# DAC_GainOutputStage6.net
KiCad netlist of a schematic drawn in EAGLE
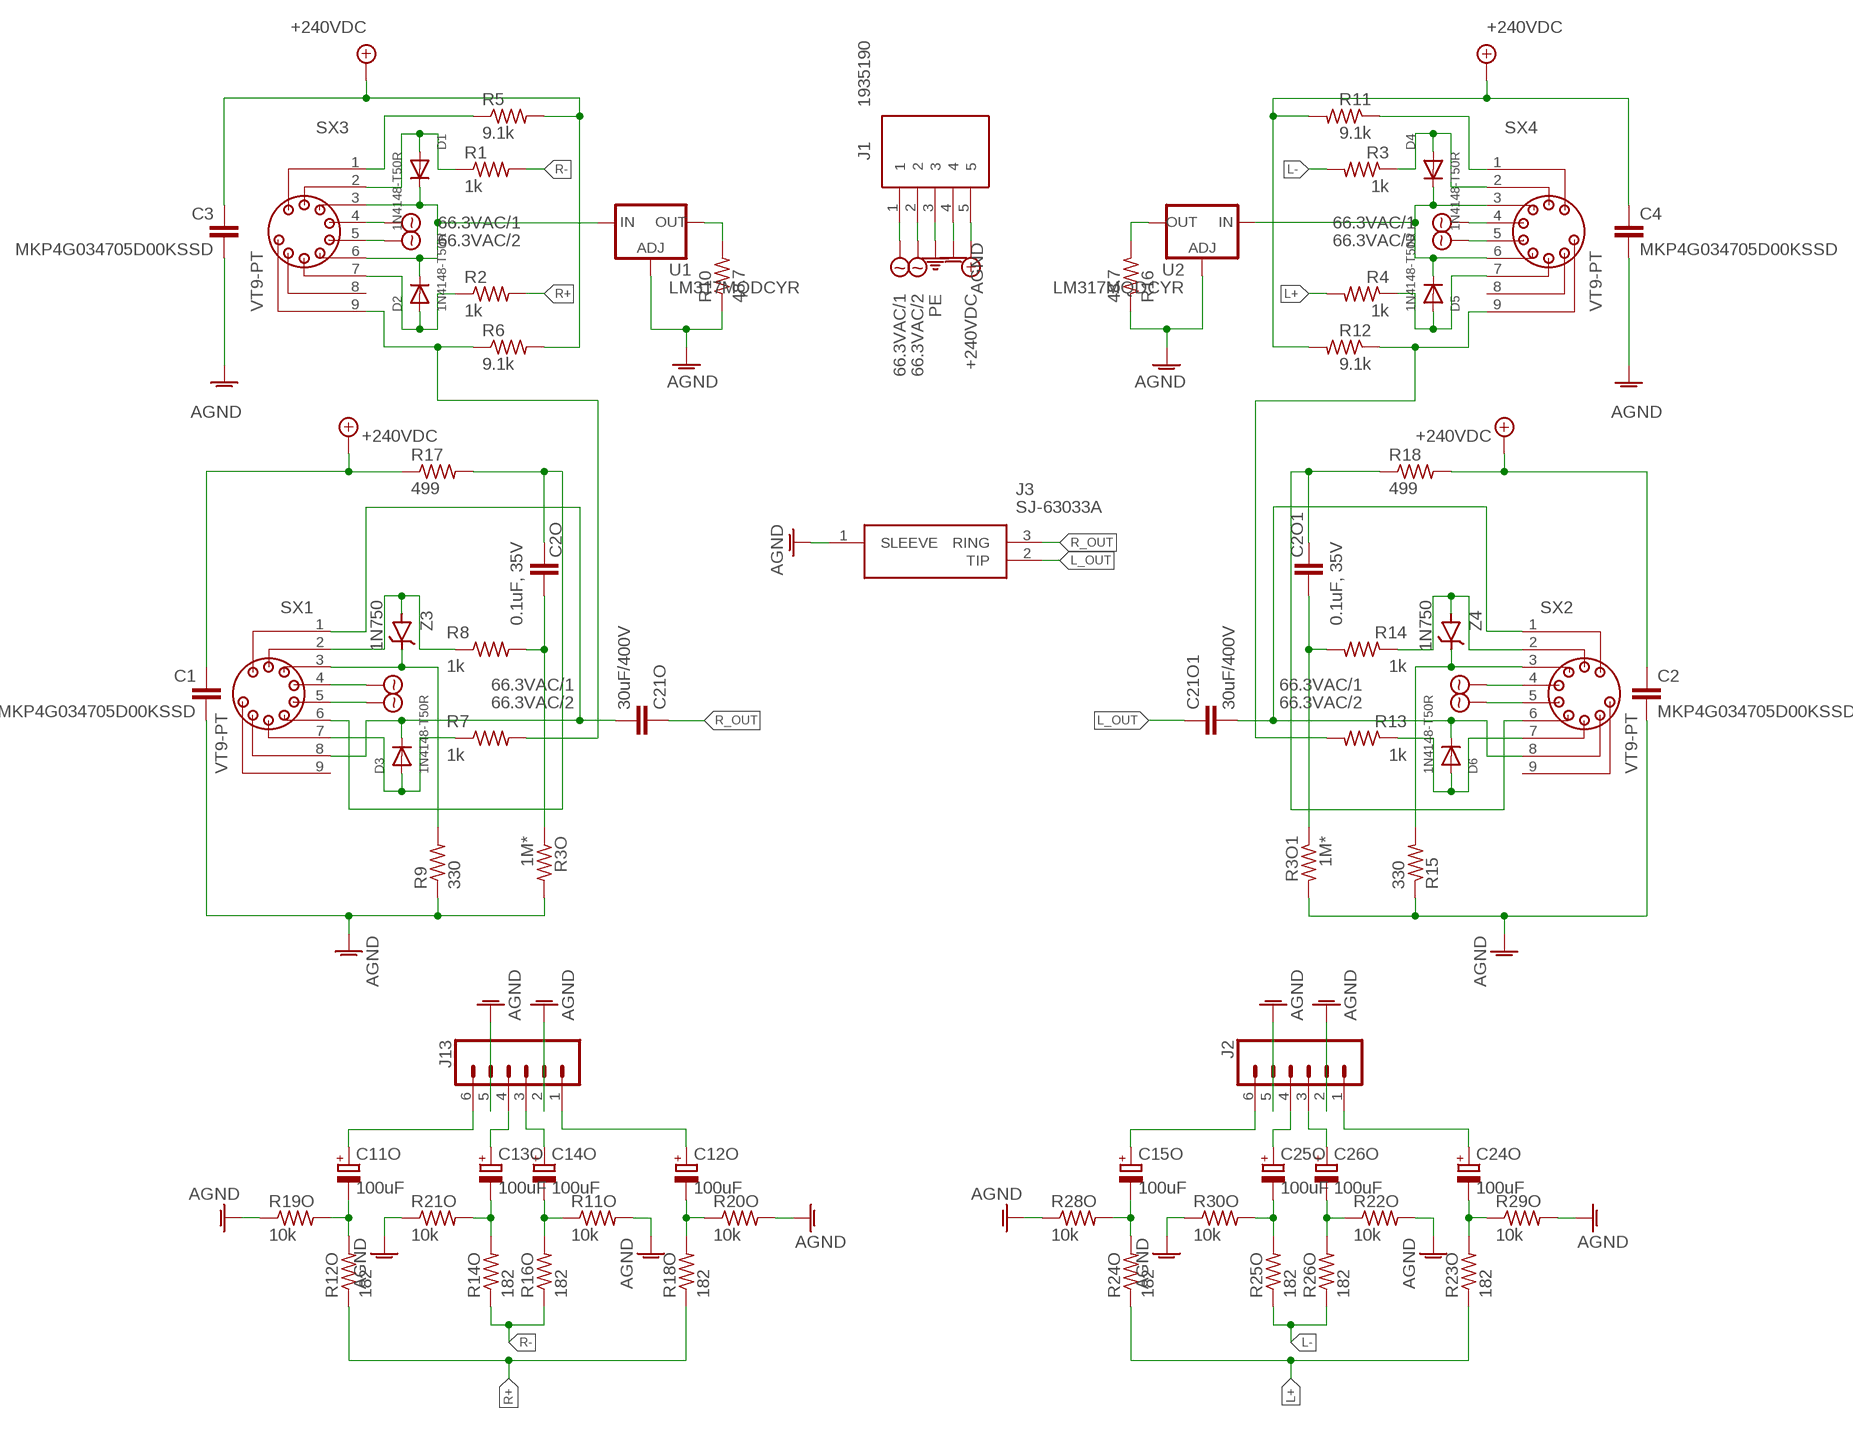
[diagram p0: schematic, sheet 1]

(export (version "E")
  (design (tool "Eeschema 10.0.6"))
  (components
    (comp (ref "C1")
      (value "MKP4G034705D00KSSD")
      (footprint "eagle-import:MKP4G034705D00KSSD")
      (fields (field (name "MOUSER_PART_NUMBER") "505-MKP4G034705DKSSD"))
      (libsource (lib "eagle-import") (part "MKP4G034705D00KSSD"))
    )
    (comp (ref "C2")
      (value "MKP4G034705D00KSSD")
      (footprint "eagle-import:MKP4G034705D00KSSD")
      (fields (field (name "MOUSER_PART_NUMBER") "505-MKP4G034705DKSSD"))
      (libsource (lib "eagle-import") (part "MKP4G034705D00KSSD"))
    )
    (comp (ref "C2O")
      (value "0.1uF, 35V")
      (footprint "eagle-import:MKS4B031002A00JC00")
      (fields
        (field (name "MANUFACTURER_PART_NUMBER") "MKS4B031002A00JC00")
        (field (name "MOUSER_PART_NUMBER") "505-MKS4B0312AJC")
      )
      (libsource (lib "eagle-import") (part "MKS4B031002A00JC00"))
    )
    (comp (ref "C2O1")
      (value "0.1uF, 35V")
      (footprint "eagle-import:MKS4B031002A00JC00")
      (fields
        (field (name "MANUFACTURER_PART_NUMBER") "MKS4B031002A00JC00")
        (field (name "MOUSER_PART_NUMBER") "505-MKS4B0312AJC")
      )
      (libsource (lib "eagle-import") (part "MKS4B031002A00JC00"))
    )
    (comp (ref "C3")
      (value "MKP4G034705D00KSSD")
      (footprint "eagle-import:MKP4G034705D00KSSD")
      (fields (field (name "MOUSER_PART_NUMBER") "505-MKP4G034705DKSSD"))
      (libsource (lib "eagle-import") (part "MKP4G034705D00KSSD"))
    )
    (comp (ref "C4")
      (value "MKP4G034705D00KSSD")
      (footprint "eagle-import:MKP4G034705D00KSSD")
      (fields (field (name "MOUSER_PART_NUMBER") "505-MKP4G034705DKSSD"))
      (libsource (lib "eagle-import") (part "MKP4G034705D00KSSD"))
    )
    (comp (ref "C11O")
      (value "100uF")
      (footprint "eagle-import:CAPPRD350W60D825H1300")
      (fields
        (field (name "ARROW_PART_NUMBER") "UFW1H101MPD1TD")
        (field (name "MOUSER_PART_NUMBER") "647-UFW1H101MPD1TD")
      )
      (libsource (lib "eagle-import") (part "UFW1H101MPD1TD"))
    )
    (comp (ref "C12O")
      (value "100uF")
      (footprint "eagle-import:CAPPRD350W60D825H1300")
      (fields
        (field (name "ARROW_PART_NUMBER") "UFW1H101MPD1TD")
        (field (name "MOUSER_PART_NUMBER") "647-UFW1H101MPD1TD")
      )
      (libsource (lib "eagle-import") (part "UFW1H101MPD1TD"))
    )
    (comp (ref "C13O")
      (value "100uF")
      (footprint "eagle-import:CAPPRD350W60D825H1300")
      (fields
        (field (name "ARROW_PART_NUMBER") "UFW1H101MPD1TD")
        (field (name "MOUSER_PART_NUMBER") "647-UFW1H101MPD1TD")
      )
      (libsource (lib "eagle-import") (part "UFW1H101MPD1TD"))
    )
    (comp (ref "C14O")
      (value "100uF")
      (footprint "eagle-import:CAPPRD350W60D825H1300")
      (fields
        (field (name "ARROW_PART_NUMBER") "UFW1H101MPD1TD")
        (field (name "MOUSER_PART_NUMBER") "647-UFW1H101MPD1TD")
      )
      (libsource (lib "eagle-import") (part "UFW1H101MPD1TD"))
    )
    (comp (ref "C15O")
      (value "100uF")
      (footprint "eagle-import:CAPPRD350W60D825H1300")
      (fields
        (field (name "ARROW_PART_NUMBER") "UFW1H101MPD1TD")
        (field (name "MOUSER_PART_NUMBER") "647-UFW1H101MPD1TD")
      )
      (libsource (lib "eagle-import") (part "UFW1H101MPD1TD"))
    )
    (comp (ref "C21O")
      (value "30uF/400V")
      (footprint "eagle-import:DCP4G053006ID2KSSD")
      (fields
        (field (name "MANUFACTURER_PART_NUMBER") "DCP4G053006ID2KSSD")
        (field (name "MOUSER_PART_NUMBER") "505-DCP4G0536ID2KSSD")
      )
      (libsource (lib "eagle-import") (part "DCP4G053006ID2KSSD"))
    )
    (comp (ref "C21O1")
      (value "30uF/400V")
      (footprint "eagle-import:DCP4G053006ID2KSSD")
      (fields
        (field (name "MANUFACTURER_PART_NUMBER") "DCP4G053006ID2KSSD")
        (field (name "MOUSER_PART_NUMBER") "505-DCP4G0536ID2KSSD")
      )
      (libsource (lib "eagle-import") (part "DCP4G053006ID2KSSD"))
    )
    (comp (ref "C24O")
      (value "100uF")
      (footprint "eagle-import:CAPPRD350W60D825H1300")
      (fields
        (field (name "ARROW_PART_NUMBER") "UFW1H101MPD1TD")
        (field (name "MOUSER_PART_NUMBER") "647-UFW1H101MPD1TD")
      )
      (libsource (lib "eagle-import") (part "UFW1H101MPD1TD"))
    )
    (comp (ref "C25O")
      (value "100uF")
      (footprint "eagle-import:CAPPRD350W60D825H1300")
      (fields
        (field (name "ARROW_PART_NUMBER") "UFW1H101MPD1TD")
        (field (name "MOUSER_PART_NUMBER") "647-UFW1H101MPD1TD")
      )
      (libsource (lib "eagle-import") (part "UFW1H101MPD1TD"))
    )
    (comp (ref "C26O")
      (value "100uF")
      (footprint "eagle-import:CAPPRD350W60D825H1300")
      (fields
        (field (name "ARROW_PART_NUMBER") "UFW1H101MPD1TD")
        (field (name "MOUSER_PART_NUMBER") "647-UFW1H101MPD1TD")
      )
      (libsource (lib "eagle-import") (part "UFW1H101MPD1TD"))
    )
    (comp (ref "D1")
      (value "1N4148-T50R")
      (footprint "eagle-import:DIOAD1068W53L380D172")
      (fields (field (name "MOUSER_PART_NUMBER") "512-1N4148T50R"))
      (libsource (lib "eagle-import") (part "1N4148-T50R"))
    )
    (comp (ref "D2")
      (value "1N4148-T50R")
      (footprint "eagle-import:DIOAD1068W53L380D172")
      (fields (field (name "MOUSER_PART_NUMBER") "512-1N4148T50R"))
      (libsource (lib "eagle-import") (part "1N4148-T50R"))
    )
    (comp (ref "D3")
      (value "1N4148-T50R")
      (footprint "eagle-import:DIOAD1068W53L380D172")
      (fields (field (name "MOUSER_PART_NUMBER") "512-1N4148T50R"))
      (libsource (lib "eagle-import") (part "1N4148-T50R"))
    )
    (comp (ref "D4")
      (value "1N4148-T50R")
      (footprint "eagle-import:DIOAD1068W53L380D172")
      (fields (field (name "MOUSER_PART_NUMBER") "512-1N4148T50R"))
      (libsource (lib "eagle-import") (part "1N4148-T50R"))
    )
    (comp (ref "D5")
      (value "1N4148-T50R")
      (footprint "eagle-import:DIOAD1068W53L380D172")
      (fields (field (name "MOUSER_PART_NUMBER") "512-1N4148T50R"))
      (libsource (lib "eagle-import") (part "1N4148-T50R"))
    )
    (comp (ref "D6")
      (value "1N4148-T50R")
      (footprint "eagle-import:DIOAD1068W53L380D172")
      (fields (field (name "MOUSER_PART_NUMBER") "512-1N4148T50R"))
      (libsource (lib "eagle-import") (part "1N4148-T50R"))
    )
    (comp (ref "J1")
      (value "1935190")
      (footprint "eagle-import:1935190")
      (fields (field (name "MOUSER_PART_NUMBER") "651-1935190"))
      (libsource (lib "eagle-import") (part "1935190"))
    )
    (comp (ref "J2")
      (value "CONN_06SILK_FEMALE_PTH")
      (footprint "eagle-import:1X06")
      (libsource (lib "eagle-import") (part "CONN_06SILK_FEMALE_PTH"))
    )
    (comp (ref "J3")
      (value "SJ-63033A")
      (footprint "eagle-import:SJ63033A")
      (libsource (lib "eagle-import") (part "SJ-63033A"))
    )
    (comp (ref "J13")
      (value "CONN_06SILK_FEMALE_PTH")
      (footprint "eagle-import:1X06")
      (libsource (lib "eagle-import") (part "CONN_06SILK_FEMALE_PTH"))
    )
    (comp (ref "R1")
      (value "1k")
      (footprint "eagle-import:0207_10")
      (fields
        (field (name "MANUFACTURER_PART_NUMBER") "LR1F1K0")
        (field (name "MOUSER_PART_NUMBER") "279-LR1F1K0")
      )
      (libsource (lib "eagle-import") (part "LR1F1K0"))
    )
    (comp (ref "R2")
      (value "1k")
      (footprint "eagle-import:0207_10")
      (fields
        (field (name "MANUFACTURER_PART_NUMBER") "LR1F1K0")
        (field (name "MOUSER_PART_NUMBER") "279-LR1F1K0")
      )
      (libsource (lib "eagle-import") (part "LR1F1K0"))
    )
    (comp (ref "R3")
      (value "1k")
      (footprint "eagle-import:0207_10")
      (fields
        (field (name "MANUFACTURER_PART_NUMBER") "LR1F1K0")
        (field (name "MOUSER_PART_NUMBER") "279-LR1F1K0")
      )
      (libsource (lib "eagle-import") (part "LR1F1K0"))
    )
    (comp (ref "R3O")
      (value "1M*")
      (footprint "eagle-import:0207_10")
      (fields
        (field (name "MANUFACTURER_PART_NUMBER") "LR1F1M0")
        (field (name "MOUSER_PART_NUMBER") "279-LR1F1M0")
      )
      (libsource (lib "eagle-import") (part "LR1F1M0"))
    )
    (comp (ref "R3O1")
      (value "1M*")
      (footprint "eagle-import:0207_10")
      (fields
        (field (name "MANUFACTURER_PART_NUMBER") "LR1F1M0")
        (field (name "MOUSER_PART_NUMBER") "279-LR1F1M0")
      )
      (libsource (lib "eagle-import") (part "LR1F1M0"))
    )
    (comp (ref "R4")
      (value "1k")
      (footprint "eagle-import:0207_10")
      (fields
        (field (name "MANUFACTURER_PART_NUMBER") "LR1F1K0")
        (field (name "MOUSER_PART_NUMBER") "279-LR1F1K0")
      )
      (libsource (lib "eagle-import") (part "LR1F1K0"))
    )
    (comp (ref "R5")
      (value "9.1k")
      (footprint "eagle-import:0411_15")
      (fields
        (field (name "MANUFACTURER_PART_NUMBER") "PR02000209101FA100")
        (field (name "MOUSER_PART_NUMBER") "594-PR02000209101FA1")
      )
      (libsource (lib "eagle-import") (part "PR02000209101FA100"))
    )
    (comp (ref "R6")
      (value "9.1k")
      (footprint "eagle-import:0411_15")
      (fields
        (field (name "MANUFACTURER_PART_NUMBER") "PR02000209101FA100")
        (field (name "MOUSER_PART_NUMBER") "594-PR02000209101FA1")
      )
      (libsource (lib "eagle-import") (part "PR02000209101FA100"))
    )
    (comp (ref "R7")
      (value "1k")
      (footprint "eagle-import:0207_10")
      (fields
        (field (name "MANUFACTURER_PART_NUMBER") "LR1F1K0")
        (field (name "MOUSER_PART_NUMBER") "279-LR1F1K0")
      )
      (libsource (lib "eagle-import") (part "LR1F1K0"))
    )
    (comp (ref "R8")
      (value "1k")
      (footprint "eagle-import:0207_10")
      (fields
        (field (name "MANUFACTURER_PART_NUMBER") "LR1F1K0")
        (field (name "MOUSER_PART_NUMBER") "279-LR1F1K0")
      )
      (libsource (lib "eagle-import") (part "LR1F1K0"))
    )
    (comp (ref "R9")
      (value "330")
      (footprint "eagle-import:0207_10")
      (fields
        (field (name "MANUFACTURER_PART_NUMBER") "LR1F330R")
        (field (name "MOUSER_PART_NUMBER") "279-LR1F330R")
      )
      (libsource (lib "eagle-import") (part "LR1F330R"))
    )
    (comp (ref "R10")
      (value "48.7")
      (footprint "eagle-import:0207_10")
      (fields
        (field (name "MANUFACTURER_PART_NUMBER") "RN55D48R7FB14")
        (field (name "MOUSER_PART_NUMBER") "71-RN55D-F-48.7")
      )
      (libsource (lib "eagle-import") (part "RN55D48R7FB14"))
    )
    (comp (ref "R11")
      (value "9.1k")
      (footprint "eagle-import:0411_15")
      (fields
        (field (name "MANUFACTURER_PART_NUMBER") "PR02000209101FA100")
        (field (name "MOUSER_PART_NUMBER") "594-PR02000209101FA1")
      )
      (libsource (lib "eagle-import") (part "PR02000209101FA100"))
    )
    (comp (ref "R11O")
      (value "10k")
      (footprint "eagle-import:0207_10")
      (fields
        (field (name "MANUFACTURER_PART_NUMBER") "LR1F10K")
        (field (name "MOUSER_PART_NUMBER") "279-LR1F10K")
      )
      (libsource (lib "eagle-import") (part "LR1F10K"))
    )
    (comp (ref "R12")
      (value "9.1k")
      (footprint "eagle-import:0411_15")
      (fields
        (field (name "MANUFACTURER_PART_NUMBER") "PR02000209101FA100")
        (field (name "MOUSER_PART_NUMBER") "594-PR02000209101FA1")
      )
      (libsource (lib "eagle-import") (part "PR02000209101FA100"))
    )
    (comp (ref "R12O")
      (value "182")
      (footprint "eagle-import:0207_10")
      (fields
        (field (name "MANUFACTURER") "Yageo")
        (field (name "MANUFACTURER_PART_NUMBER") "MF0207FTE52-182R")
        (field (name "MOUSER_PART_NUMBER") "603-MF0207FTE52-182R")
      )
      (libsource (lib "eagle-import") (part "MF0207FTE52-182R"))
    )
    (comp (ref "R13")
      (value "1k")
      (footprint "eagle-import:0207_10")
      (fields
        (field (name "MANUFACTURER_PART_NUMBER") "LR1F1K0")
        (field (name "MOUSER_PART_NUMBER") "279-LR1F1K0")
      )
      (libsource (lib "eagle-import") (part "LR1F1K0"))
    )
    (comp (ref "R14")
      (value "1k")
      (footprint "eagle-import:0207_10")
      (fields
        (field (name "MANUFACTURER_PART_NUMBER") "LR1F1K0")
        (field (name "MOUSER_PART_NUMBER") "279-LR1F1K0")
      )
      (libsource (lib "eagle-import") (part "LR1F1K0"))
    )
    (comp (ref "R14O")
      (value "182")
      (footprint "eagle-import:0207_10")
      (fields
        (field (name "MANUFACTURER") "Yageo")
        (field (name "MANUFACTURER_PART_NUMBER") "MF0207FTE52-182R")
        (field (name "MOUSER_PART_NUMBER") "603-MF0207FTE52-182R")
      )
      (libsource (lib "eagle-import") (part "MF0207FTE52-182R"))
    )
    (comp (ref "R15")
      (value "330")
      (footprint "eagle-import:0207_10")
      (fields
        (field (name "MANUFACTURER_PART_NUMBER") "LR1F330R")
        (field (name "MOUSER_PART_NUMBER") "279-LR1F330R")
      )
      (libsource (lib "eagle-import") (part "LR1F330R"))
    )
    (comp (ref "R16")
      (value "48.7")
      (footprint "eagle-import:0207_10")
      (fields
        (field (name "MANUFACTURER_PART_NUMBER") "RN55D48R7FB14")
        (field (name "MOUSER_PART_NUMBER") "71-RN55D-F-48.7")
      )
      (libsource (lib "eagle-import") (part "RN55D48R7FB14"))
    )
    (comp (ref "R16O")
      (value "182")
      (footprint "eagle-import:0207_10")
      (fields
        (field (name "MANUFACTURER") "Yageo")
        (field (name "MANUFACTURER_PART_NUMBER") "MF0207FTE52-182R")
        (field (name "MOUSER_PART_NUMBER") "603-MF0207FTE52-182R")
      )
      (libsource (lib "eagle-import") (part "MF0207FTE52-182R"))
    )
    (comp (ref "R17")
      (value "499")
      (footprint "eagle-import:0411_15")
      (fields
        (field (name "MANUFACTURER_PART_NUMBER") "PR02000204990FA100")
        (field (name "MOUSER_PART_NUMBER") "594-PR02000204990FA1")
      )
      (libsource (lib "eagle-import") (part "PR02000204990FA100"))
    )
    (comp (ref "R18")
      (value "499")
      (footprint "eagle-import:0411_15")
      (fields
        (field (name "MANUFACTURER_PART_NUMBER") "PR02000204990FA100")
        (field (name "MOUSER_PART_NUMBER") "594-PR02000204990FA1")
      )
      (libsource (lib "eagle-import") (part "PR02000204990FA100"))
    )
    (comp (ref "R18O")
      (value "182")
      (footprint "eagle-import:0207_10")
      (fields
        (field (name "MANUFACTURER") "Yageo")
        (field (name "MANUFACTURER_PART_NUMBER") "MF0207FTE52-182R")
        (field (name "MOUSER_PART_NUMBER") "603-MF0207FTE52-182R")
      )
      (libsource (lib "eagle-import") (part "MF0207FTE52-182R"))
    )
    (comp (ref "R19O")
      (value "10k")
      (footprint "eagle-import:0207_10")
      (fields
        (field (name "MANUFACTURER_PART_NUMBER") "LR1F10K")
        (field (name "MOUSER_PART_NUMBER") "279-LR1F10K")
      )
      (libsource (lib "eagle-import") (part "LR1F10K"))
    )
    (comp (ref "R20O")
      (value "10k")
      (footprint "eagle-import:0207_10")
      (fields
        (field (name "MANUFACTURER_PART_NUMBER") "LR1F10K")
        (field (name "MOUSER_PART_NUMBER") "279-LR1F10K")
      )
      (libsource (lib "eagle-import") (part "LR1F10K"))
    )
    (comp (ref "R21O")
      (value "10k")
      (footprint "eagle-import:0207_10")
      (fields
        (field (name "MANUFACTURER_PART_NUMBER") "LR1F10K")
        (field (name "MOUSER_PART_NUMBER") "279-LR1F10K")
      )
      (libsource (lib "eagle-import") (part "LR1F10K"))
    )
    (comp (ref "R22O")
      (value "10k")
      (footprint "eagle-import:0207_10")
      (fields
        (field (name "MANUFACTURER_PART_NUMBER") "LR1F10K")
        (field (name "MOUSER_PART_NUMBER") "279-LR1F10K")
      )
      (libsource (lib "eagle-import") (part "LR1F10K"))
    )
    (comp (ref "R23O")
      (value "182")
      (footprint "eagle-import:0207_10")
      (fields
        (field (name "MANUFACTURER") "Yageo")
        (field (name "MANUFACTURER_PART_NUMBER") "MF0207FTE52-182R")
        (field (name "MOUSER_PART_NUMBER") "603-MF0207FTE52-182R")
      )
      (libsource (lib "eagle-import") (part "MF0207FTE52-182R"))
    )
    (comp (ref "R24O")
      (value "182")
      (footprint "eagle-import:0207_10")
      (fields
        (field (name "MANUFACTURER") "Yageo")
        (field (name "MANUFACTURER_PART_NUMBER") "MF0207FTE52-182R")
        (field (name "MOUSER_PART_NUMBER") "603-MF0207FTE52-182R")
      )
      (libsource (lib "eagle-import") (part "MF0207FTE52-182R"))
    )
    (comp (ref "R25O")
      (value "182")
      (footprint "eagle-import:0207_10")
      (fields
        (field (name "MANUFACTURER") "Yageo")
        (field (name "MANUFACTURER_PART_NUMBER") "MF0207FTE52-182R")
        (field (name "MOUSER_PART_NUMBER") "603-MF0207FTE52-182R")
      )
      (libsource (lib "eagle-import") (part "MF0207FTE52-182R"))
    )
    (comp (ref "R26O")
      (value "182")
      (footprint "eagle-import:0207_10")
      (fields
        (field (name "MANUFACTURER") "Yageo")
        (field (name "MANUFACTURER_PART_NUMBER") "MF0207FTE52-182R")
        (field (name "MOUSER_PART_NUMBER") "603-MF0207FTE52-182R")
      )
      (libsource (lib "eagle-import") (part "MF0207FTE52-182R"))
    )
    (comp (ref "R28O")
      (value "10k")
      (footprint "eagle-import:0207_10")
      (fields
        (field (name "MANUFACTURER_PART_NUMBER") "LR1F10K")
        (field (name "MOUSER_PART_NUMBER") "279-LR1F10K")
      )
      (libsource (lib "eagle-import") (part "LR1F10K"))
    )
    (comp (ref "R29O")
      (value "10k")
      (footprint "eagle-import:0207_10")
      (fields
        (field (name "MANUFACTURER_PART_NUMBER") "LR1F10K")
        (field (name "MOUSER_PART_NUMBER") "279-LR1F10K")
      )
      (libsource (lib "eagle-import") (part "LR1F10K"))
    )
    (comp (ref "R30O")
      (value "10k")
      (footprint "eagle-import:0207_10")
      (fields
        (field (name "MANUFACTURER_PART_NUMBER") "LR1F10K")
        (field (name "MOUSER_PART_NUMBER") "279-LR1F10K")
      )
      (libsource (lib "eagle-import") (part "LR1F10K"))
    )
    (comp (ref "SX1")
      (value "VT9-PT")
      (footprint "eagle-import:VT9-PT")
      (libsource (lib "eagle-import") (part "VT9-PT"))
    )
    (comp (ref "SX2")
      (value "VT9-PT")
      (footprint "eagle-import:VT9-PT")
      (libsource (lib "eagle-import") (part "VT9-PT"))
    )
    (comp (ref "SX3")
      (value "VT9-PT")
      (footprint "eagle-import:VT9-PT")
      (libsource (lib "eagle-import") (part "VT9-PT"))
    )
    (comp (ref "SX4")
      (value "VT9-PT")
      (footprint "eagle-import:VT9-PT")
      (libsource (lib "eagle-import") (part "VT9-PT"))
    )
    (comp (ref "U1")
      (value "LM317MQDCYR")
      (footprint "eagle-import:SOT230P700X180-4N")
      (fields (field (name "MOUSER_PART_NUMBER") "595-LM317MQDCYR"))
      (libsource (lib "eagle-import") (part "LM317MQDCYR"))
    )
    (comp (ref "U2")
      (value "LM317MQDCYR")
      (footprint "eagle-import:SOT230P700X180-4N")
      (fields (field (name "MOUSER_PART_NUMBER") "595-LM317MQDCYR"))
      (libsource (lib "eagle-import") (part "LM317MQDCYR"))
    )
    (comp (ref "Z3")
      (value "1N750")
      (footprint "eagle-import:DIOAD1256W56L444D203")
      (fields (field (name "MOUSER_PART_NUMBER") "494-1N750(DO-35)"))
      (libsource (lib "eagle-import") (part "1N750"))
    )
    (comp (ref "Z4")
      (value "1N750")
      (footprint "eagle-import:DIOAD1256W56L444D203")
      (fields (field (name "MOUSER_PART_NUMBER") "494-1N750(DO-35)"))
      (libsource (lib "eagle-import") (part "1N750"))
    )
  )
  (nets
    (net (code "1") (name "+240VDC") (class "Default")
      (node (ref "C1") (pin "1") (pinfunction "1_1") (pintype "passive"))
      (node (ref "C2") (pin "1") (pinfunction "1_1") (pintype "passive"))
      (node (ref "C3") (pin "1") (pinfunction "1_1") (pintype "passive"))
      (node (ref "C4") (pin "1") (pinfunction "1_1") (pintype "passive"))
      (node (ref "J1") (pin "5") (pinfunction "5_5") (pintype "bidirectional"))
      (node (ref "R11") (pin "2") (pinfunction "2_2") (pintype "passive"))
      (node (ref "R12") (pin "2") (pinfunction "2_2") (pintype "passive"))
      (node (ref "R17") (pin "1") (pinfunction "1_1") (pintype "passive"))
      (node (ref "R18") (pin "2") (pinfunction "2_2") (pintype "passive"))
      (node (ref "R5") (pin "2") (pinfunction "2_2") (pintype "passive"))
      (node (ref "R6") (pin "2") (pinfunction "2_2") (pintype "passive"))
    )
    (net (code "2") (name "66.3VAC{slash}1") (class "Default")
      (node (ref "J1") (pin "1") (pinfunction "1_1") (pintype "bidirectional"))
      (node (ref "SX1") (pin "4") (pinfunction "4_4") (pintype "passive"))
      (node (ref "SX2") (pin "4") (pinfunction "4_4") (pintype "passive"))
      (node (ref "SX3") (pin "4") (pinfunction "4_4") (pintype "passive"))
      (node (ref "SX4") (pin "4") (pinfunction "4_4") (pintype "passive"))
    )
    (net (code "3") (name "66.3VAC{slash}2") (class "Default")
      (node (ref "J1") (pin "2") (pinfunction "2_2") (pintype "bidirectional"))
      (node (ref "SX1") (pin "5") (pinfunction "5_5") (pintype "passive"))
      (node (ref "SX2") (pin "5") (pinfunction "5_5") (pintype "passive"))
      (node (ref "SX3") (pin "5") (pinfunction "5_5") (pintype "passive"))
      (node (ref "SX4") (pin "5") (pinfunction "5_5") (pintype "passive"))
    )
    (net (code "4") (name "AGND") (class "Default")
      (node (ref "C1") (pin "2") (pinfunction "2_2") (pintype "passive"))
      (node (ref "C2") (pin "2") (pinfunction "2_2") (pintype "passive"))
      (node (ref "C3") (pin "2") (pinfunction "2_2") (pintype "passive"))
      (node (ref "C4") (pin "2") (pinfunction "2_2") (pintype "passive"))
      (node (ref "J1") (pin "4") (pinfunction "4_4") (pintype "bidirectional"))
      (node (ref "J13") (pin "2") (pinfunction "2_2") (pintype "passive"))
      (node (ref "J13") (pin "5") (pinfunction "5_5") (pintype "passive"))
      (node (ref "J2") (pin "2") (pinfunction "2_2") (pintype "passive"))
      (node (ref "J2") (pin "5") (pinfunction "5_5") (pintype "passive"))
      (node (ref "J3") (pin "1") (pinfunction "SLEEVE_1") (pintype "bidirectional"))
      (node (ref "R10") (pin "1") (pinfunction "1_1") (pintype "passive"))
      (node (ref "R11O") (pin "2") (pinfunction "2_2") (pintype "passive"))
      (node (ref "R15") (pin "1") (pinfunction "1_1") (pintype "passive"))
      (node (ref "R16") (pin "1") (pinfunction "1_1") (pintype "passive"))
      (node (ref "R19O") (pin "1") (pinfunction "1_1") (pintype "passive"))
      (node (ref "R20O") (pin "2") (pinfunction "2_2") (pintype "passive"))
      (node (ref "R21O") (pin "1") (pinfunction "1_1") (pintype "passive"))
      (node (ref "R22O") (pin "2") (pinfunction "2_2") (pintype "passive"))
      (node (ref "R28O") (pin "1") (pinfunction "1_1") (pintype "passive"))
      (node (ref "R29O") (pin "2") (pinfunction "2_2") (pintype "passive"))
      (node (ref "R30O") (pin "1") (pinfunction "1_1") (pintype "passive"))
      (node (ref "R3O") (pin "2") (pinfunction "2_2") (pintype "passive"))
      (node (ref "R3O1") (pin "2") (pinfunction "2_2") (pintype "passive"))
      (node (ref "R9") (pin "1") (pinfunction "1_1") (pintype "passive"))
      (node (ref "U1") (pin "1") (pinfunction "ADJ_1") (pintype "input"))
      (node (ref "U2") (pin "1") (pinfunction "ADJ_1") (pintype "input"))
    )
    (net (code "5") (name "L+") (class "Default")
      (node (ref "R23O") (pin "1") (pinfunction "1_1") (pintype "passive"))
      (node (ref "R24O") (pin "1") (pinfunction "1_1") (pintype "passive"))
      (node (ref "R4") (pin "2") (pinfunction "2_2") (pintype "passive"))
    )
    (net (code "6") (name "L-") (class "Default")
      (node (ref "R25O") (pin "1") (pinfunction "1_1") (pintype "passive"))
      (node (ref "R26O") (pin "1") (pinfunction "1_1") (pintype "passive"))
      (node (ref "R3") (pin "2") (pinfunction "2_2") (pintype "passive"))
    )
    (net (code "7") (name "L_OUT") (class "Default")
      (node (ref "C21O1") (pin "1") (pinfunction "1_1") (pintype "passive"))
      (node (ref "J3") (pin "2") (pinfunction "TIP_2") (pintype "bidirectional"))
    )
    (net (code "8") (name "Net-(C2O-Pad1)") (class "Default")
      (node (ref "C2O") (pin "1") (pinfunction "1_1") (pintype "passive"))
      (node (ref "R17") (pin "2") (pinfunction "2_2") (pintype "passive"))
      (node (ref "SX1") (pin "6") (pinfunction "6_6") (pintype "passive"))
    )
    (net (code "9") (name "Net-(C2O-Pad2)") (class "Default")
      (node (ref "C2O") (pin "2") (pinfunction "2_2") (pintype "passive"))
      (node (ref "R3O") (pin "1") (pinfunction "1_1") (pintype "passive"))
      (node (ref "R8") (pin "2") (pinfunction "2_2") (pintype "passive"))
    )
    (net (code "10") (name "Net-(C2O1-Pad1)") (class "Default")
      (node (ref "C2O1") (pin "1") (pinfunction "1_1") (pintype "passive"))
      (node (ref "R18") (pin "1") (pinfunction "1_1") (pintype "passive"))
      (node (ref "SX2") (pin "6") (pinfunction "6_6") (pintype "passive"))
    )
    (net (code "11") (name "Net-(C2O1-Pad2)") (class "Default")
      (node (ref "C2O1") (pin "2") (pinfunction "2_2") (pintype "passive"))
      (node (ref "R14") (pin "2") (pinfunction "2_2") (pintype "passive"))
      (node (ref "R3O1") (pin "1") (pinfunction "1_1") (pintype "passive"))
    )
    (net (code "12") (name "Net-(C11O-+)") (class "Default")
      (node (ref "C11O") (pin "1") (pinfunction "+_1") (pintype "passive"))
      (node (ref "J13") (pin "6") (pinfunction "6_6") (pintype "passive"))
    )
    (net (code "13") (name "Net-(C11O--)") (class "Default")
      (node (ref "C11O") (pin "2") (pinfunction "-_2") (pintype "passive"))
      (node (ref "R12O") (pin "2") (pinfunction "2_2") (pintype "passive"))
      (node (ref "R19O") (pin "2") (pinfunction "2_2") (pintype "passive"))
    )
    (net (code "14") (name "Net-(C12O-+)") (class "Default")
      (node (ref "C12O") (pin "1") (pinfunction "+_1") (pintype "passive"))
      (node (ref "J13") (pin "1") (pinfunction "1_1") (pintype "passive"))
    )
    (net (code "15") (name "Net-(C12O--)") (class "Default")
      (node (ref "C12O") (pin "2") (pinfunction "-_2") (pintype "passive"))
      (node (ref "R18O") (pin "2") (pinfunction "2_2") (pintype "passive"))
      (node (ref "R20O") (pin "1") (pinfunction "1_1") (pintype "passive"))
    )
    (net (code "16") (name "Net-(C13O-+)") (class "Default")
      (node (ref "C13O") (pin "1") (pinfunction "+_1") (pintype "passive"))
      (node (ref "J13") (pin "4") (pinfunction "4_4") (pintype "passive"))
    )
    (net (code "17") (name "Net-(C13O--)") (class "Default")
      (node (ref "C13O") (pin "2") (pinfunction "-_2") (pintype "passive"))
      (node (ref "R14O") (pin "2") (pinfunction "2_2") (pintype "passive"))
      (node (ref "R21O") (pin "2") (pinfunction "2_2") (pintype "passive"))
    )
    (net (code "18") (name "Net-(C14O-+)") (class "Default")
      (node (ref "C14O") (pin "1") (pinfunction "+_1") (pintype "passive"))
      (node (ref "J13") (pin "3") (pinfunction "3_3") (pintype "passive"))
    )
    (net (code "19") (name "Net-(C14O--)") (class "Default")
      (node (ref "C14O") (pin "2") (pinfunction "-_2") (pintype "passive"))
      (node (ref "R11O") (pin "1") (pinfunction "1_1") (pintype "passive"))
      (node (ref "R16O") (pin "2") (pinfunction "2_2") (pintype "passive"))
    )
    (net (code "20") (name "Net-(C15O-+)") (class "Default")
      (node (ref "C15O") (pin "1") (pinfunction "+_1") (pintype "passive"))
      (node (ref "J2") (pin "6") (pinfunction "6_6") (pintype "passive"))
    )
    (net (code "21") (name "Net-(C15O--)") (class "Default")
      (node (ref "C15O") (pin "2") (pinfunction "-_2") (pintype "passive"))
      (node (ref "R24O") (pin "2") (pinfunction "2_2") (pintype "passive"))
      (node (ref "R28O") (pin "2") (pinfunction "2_2") (pintype "passive"))
    )
    (net (code "22") (name "Net-(C24O-+)") (class "Default")
      (node (ref "C24O") (pin "1") (pinfunction "+_1") (pintype "passive"))
      (node (ref "J2") (pin "1") (pinfunction "1_1") (pintype "passive"))
    )
    (net (code "23") (name "Net-(C24O--)") (class "Default")
      (node (ref "C24O") (pin "2") (pinfunction "-_2") (pintype "passive"))
      (node (ref "R23O") (pin "2") (pinfunction "2_2") (pintype "passive"))
      (node (ref "R29O") (pin "1") (pinfunction "1_1") (pintype "passive"))
    )
    (net (code "24") (name "Net-(C25O-+)") (class "Default")
      (node (ref "C25O") (pin "1") (pinfunction "+_1") (pintype "passive"))
      (node (ref "J2") (pin "4") (pinfunction "4_4") (pintype "passive"))
    )
    (net (code "25") (name "Net-(C25O--)") (class "Default")
      (node (ref "C25O") (pin "2") (pinfunction "-_2") (pintype "passive"))
      (node (ref "R25O") (pin "2") (pinfunction "2_2") (pintype "passive"))
      (node (ref "R30O") (pin "2") (pinfunction "2_2") (pintype "passive"))
    )
    (net (code "26") (name "Net-(C26O-+)") (class "Default")
      (node (ref "C26O") (pin "1") (pinfunction "+_1") (pintype "passive"))
      (node (ref "J2") (pin "3") (pinfunction "3_3") (pintype "passive"))
    )
    (net (code "27") (name "Net-(C26O--)") (class "Default")
      (node (ref "C26O") (pin "2") (pinfunction "-_2") (pintype "passive"))
      (node (ref "R22O") (pin "1") (pinfunction "1_1") (pintype "passive"))
      (node (ref "R26O") (pin "2") (pinfunction "2_2") (pintype "passive"))
    )
    (net (code "28") (name "Net-(D1-A)") (class "Default")
      (node (ref "D1") (pin "2") (pinfunction "A_2") (pintype "passive"))
      (node (ref "R1") (pin "1") (pinfunction "1_1") (pintype "passive"))
      (node (ref "SX3") (pin "2") (pinfunction "2_2") (pintype "passive"))
    )
    (net (code "29") (name "Net-(D1-C)") (class "Default")
      (node (ref "D1") (pin "1") (pinfunction "C_1") (pintype "passive"))
      (node (ref "D2") (pin "1") (pinfunction "C_1") (pintype "passive"))
      (node (ref "SX3") (pin "3") (pinfunction "3_3") (pintype "passive"))
      (node (ref "SX3") (pin "6") (pinfunction "6_6") (pintype "passive"))
      (node (ref "U1") (pin "3") (pinfunction "IN_3") (pintype "input"))
    )
    (net (code "30") (name "Net-(D2-A)") (class "Default")
      (node (ref "D2") (pin "2") (pinfunction "A_2") (pintype "passive"))
      (node (ref "R2") (pin "1") (pinfunction "1_1") (pintype "passive"))
      (node (ref "SX3") (pin "7") (pinfunction "7_7") (pintype "passive"))
    )
    (net (code "31") (name "Net-(D3-A)") (class "Default")
      (node (ref "D3") (pin "2") (pinfunction "A_2") (pintype "passive"))
      (node (ref "R7") (pin "1") (pinfunction "1_1") (pintype "passive"))
      (node (ref "SX1") (pin "7") (pinfunction "7_7") (pintype "passive"))
    )
    (net (code "32") (name "Net-(D3-C)") (class "Default")
      (node (ref "C21O") (pin "2") (pinfunction "2_2") (pintype "passive"))
      (node (ref "D3") (pin "1") (pinfunction "C_1") (pintype "passive"))
      (node (ref "SX1") (pin "1") (pinfunction "1_1") (pintype "passive"))
      (node (ref "SX1") (pin "8") (pinfunction "8_8") (pintype "passive"))
    )
    (net (code "33") (name "Net-(D4-A)") (class "Default")
      (node (ref "D4") (pin "2") (pinfunction "A_2") (pintype "passive"))
      (node (ref "R3") (pin "1") (pinfunction "1_1") (pintype "passive"))
      (node (ref "SX4") (pin "2") (pinfunction "2_2") (pintype "passive"))
    )
    (net (code "34") (name "Net-(D4-C)") (class "Default")
      (node (ref "D4") (pin "1") (pinfunction "C_1") (pintype "passive"))
      (node (ref "D5") (pin "1") (pinfunction "C_1") (pintype "passive"))
      (node (ref "SX4") (pin "3") (pinfunction "3_3") (pintype "passive"))
      (node (ref "SX4") (pin "6") (pinfunction "6_6") (pintype "passive"))
      (node (ref "U2") (pin "3") (pinfunction "IN_3") (pintype "input"))
    )
    (net (code "35") (name "Net-(D5-A)") (class "Default")
      (node (ref "D5") (pin "2") (pinfunction "A_2") (pintype "passive"))
      (node (ref "R4") (pin "1") (pinfunction "1_1") (pintype "passive"))
      (node (ref "SX4") (pin "7") (pinfunction "7_7") (pintype "passive"))
    )
    (net (code "36") (name "Net-(D6-A)") (class "Default")
      (node (ref "D6") (pin "2") (pinfunction "A_2") (pintype "passive"))
      (node (ref "R13") (pin "1") (pinfunction "1_1") (pintype "passive"))
      (node (ref "SX2") (pin "7") (pinfunction "7_7") (pintype "passive"))
    )
    (net (code "37") (name "Net-(D6-C)") (class "Default")
      (node (ref "C21O1") (pin "2") (pinfunction "2_2") (pintype "passive"))
      (node (ref "D6") (pin "1") (pinfunction "C_1") (pintype "passive"))
      (node (ref "SX2") (pin "1") (pinfunction "1_1") (pintype "passive"))
      (node (ref "SX2") (pin "8") (pinfunction "8_8") (pintype "passive"))
    )
    (net (code "38") (name "Net-(R5-Pad1)") (class "Default")
      (node (ref "R5") (pin "1") (pinfunction "1_1") (pintype "passive"))
      (node (ref "SX3") (pin "1") (pinfunction "1_1") (pintype "passive"))
    )
    (net (code "39") (name "Net-(R6-Pad1)") (class "Default")
      (node (ref "R6") (pin "1") (pinfunction "1_1") (pintype "passive"))
      (node (ref "R7") (pin "2") (pinfunction "2_2") (pintype "passive"))
      (node (ref "SX3") (pin "9") (pinfunction "9_9") (pintype "passive"))
    )
    (net (code "40") (name "Net-(R10-Pad2)") (class "Default")
      (node (ref "R10") (pin "2") (pinfunction "2_2") (pintype "passive"))
      (node (ref "U1") (pin "2") (pinfunction "OUT_2") (pintype "passive"))
      (node (ref "U1") (pin "4") (pinfunction "OUT_4") (pintype "passive"))
    )
    (net (code "41") (name "Net-(R11-Pad1)") (class "Default")
      (node (ref "R11") (pin "1") (pinfunction "1_1") (pintype "passive"))
      (node (ref "SX4") (pin "1") (pinfunction "1_1") (pintype "passive"))
    )
    (net (code "42") (name "Net-(R12-Pad1)") (class "Default")
      (node (ref "R12") (pin "1") (pinfunction "1_1") (pintype "passive"))
      (node (ref "R13") (pin "2") (pinfunction "2_2") (pintype "passive"))
      (node (ref "SX4") (pin "9") (pinfunction "9_9") (pintype "passive"))
    )
    (net (code "43") (name "Net-(R16-Pad2)") (class "Default")
      (node (ref "R16") (pin "2") (pinfunction "2_2") (pintype "passive"))
      (node (ref "U2") (pin "2") (pinfunction "OUT_2") (pintype "passive"))
      (node (ref "U2") (pin "4") (pinfunction "OUT_4") (pintype "passive"))
    )
    (net (code "44") (name "Net-(Z3-A)") (class "Default")
      (node (ref "R8") (pin "1") (pinfunction "1_1") (pintype "passive"))
      (node (ref "SX1") (pin "2") (pinfunction "2_2") (pintype "passive"))
      (node (ref "Z3") (pin "2") (pinfunction "A_2") (pintype "passive"))
    )
    (net (code "45") (name "Net-(Z3-C)") (class "Default")
      (node (ref "R9") (pin "2") (pinfunction "2_2") (pintype "passive"))
      (node (ref "SX1") (pin "3") (pinfunction "3_3") (pintype "passive"))
      (node (ref "Z3") (pin "1") (pinfunction "C_1") (pintype "passive"))
    )
    (net (code "46") (name "Net-(Z4-A)") (class "Default")
      (node (ref "R14") (pin "1") (pinfunction "1_1") (pintype "passive"))
      (node (ref "SX2") (pin "2") (pinfunction "2_2") (pintype "passive"))
      (node (ref "Z4") (pin "2") (pinfunction "A_2") (pintype "passive"))
    )
    (net (code "47") (name "Net-(Z4-C)") (class "Default")
      (node (ref "R15") (pin "2") (pinfunction "2_2") (pintype "passive"))
      (node (ref "SX2") (pin "3") (pinfunction "3_3") (pintype "passive"))
      (node (ref "Z4") (pin "1") (pinfunction "C_1") (pintype "passive"))
    )
    (net (code "48") (name "PE") (class "Default")
      (node (ref "J1") (pin "3") (pinfunction "3_3") (pintype "bidirectional"))
    )
    (net (code "49") (name "R+") (class "Default")
      (node (ref "R12O") (pin "1") (pinfunction "1_1") (pintype "passive"))
      (node (ref "R18O") (pin "1") (pinfunction "1_1") (pintype "passive"))
      (node (ref "R2") (pin "2") (pinfunction "2_2") (pintype "passive"))
    )
    (net (code "50") (name "R-") (class "Default")
      (node (ref "R1") (pin "2") (pinfunction "2_2") (pintype "passive"))
      (node (ref "R14O") (pin "1") (pinfunction "1_1") (pintype "passive"))
      (node (ref "R16O") (pin "1") (pinfunction "1_1") (pintype "passive"))
    )
    (net (code "51") (name "R_OUT") (class "Default")
      (node (ref "C21O") (pin "1") (pinfunction "1_1") (pintype "passive"))
      (node (ref "J3") (pin "3") (pinfunction "RING_3") (pintype "bidirectional"))
    )
    (net (code "52") (name "unconnected-(SX1-Pad9)") (class "Default")
      (node (ref "SX1") (pin "9") (pinfunction "9_9") (pintype "passive"))
    )
    (net (code "53") (name "unconnected-(SX2-Pad9)") (class "Default")
      (node (ref "SX2") (pin "9") (pinfunction "9_9") (pintype "passive"))
    )
    (net (code "54") (name "unconnected-(SX3-Pad8)") (class "Default")
      (node (ref "SX3") (pin "8") (pinfunction "8_8") (pintype "passive"))
    )
    (net (code "55") (name "unconnected-(SX4-Pad8)") (class "Default")
      (node (ref "SX4") (pin "8") (pinfunction "8_8") (pintype "passive"))
    )
  )
)
